# rapidshark-motor-connector-mk-1_1.net
KiCad netlist of a schematic drawn in EAGLE
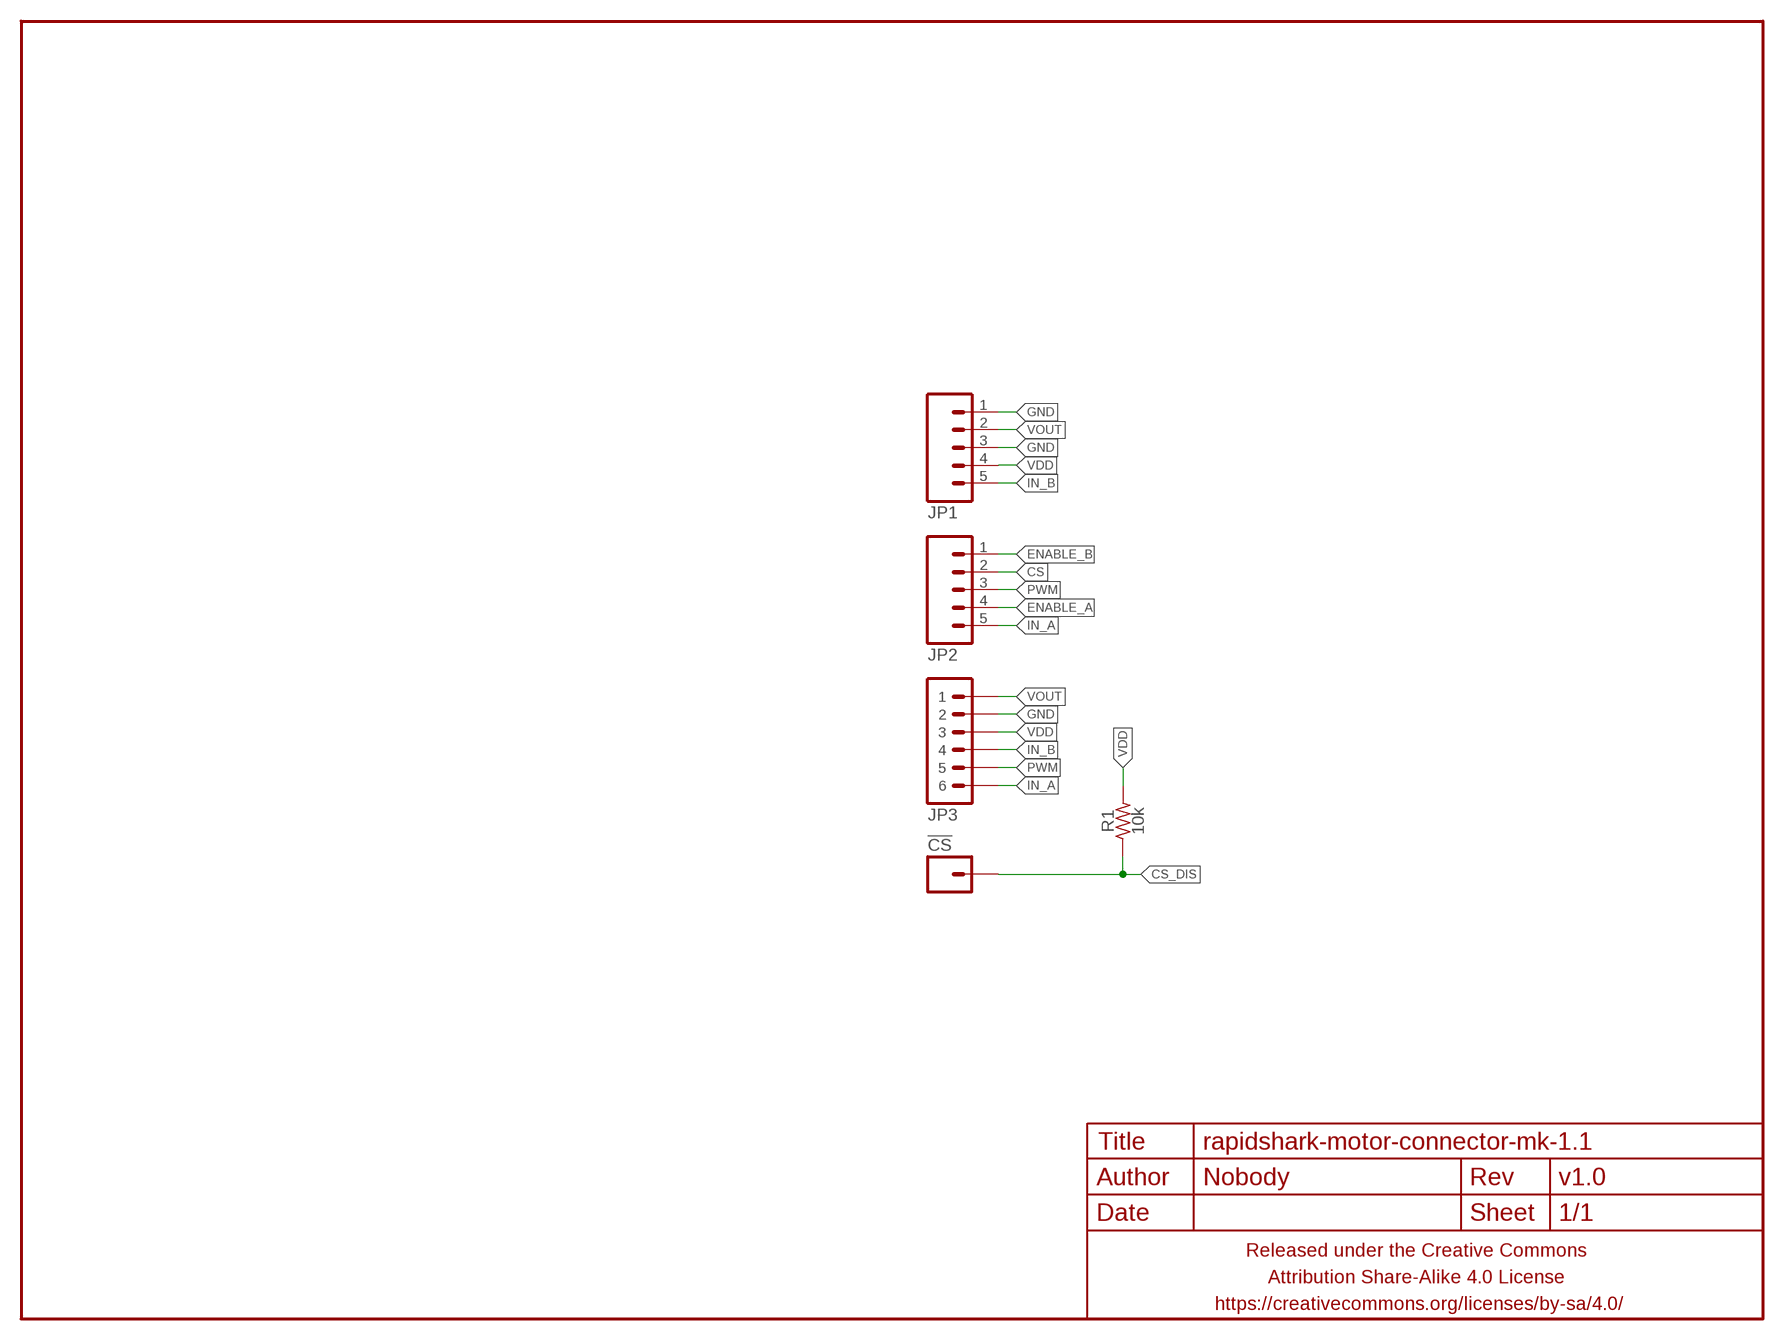
[diagram p0: schematic, sheet 1]

(export (version "E")
  (design (tool "Eeschema 10.0.6"))
  (components
    (comp (ref "!CS")
      (value "M01PTH")
      (footprint "eagle-import:1X01")
      (libsource (lib "eagle-import") (part "M01PTH"))
    )
    (comp (ref "FRAME1")
      (value "FRAME-LETTERNO_PACKAGE")
      (footprint "eagle-import:DUMMY")
      (fields (field (name "VERSION") "v1.0") (field (name "DESIGNER") "Nobody"))
      (libsource (lib "eagle-import") (part "FRAME-LETTERNO_PACKAGE"))
    )
    (comp (ref "JP1")
      (value "M05PTH")
      (footprint "eagle-import:1X05")
      (libsource (lib "eagle-import") (part "M05PTH"))
    )
    (comp (ref "JP2")
      (value "M05PTH")
      (footprint "eagle-import:1X05")
      (libsource (lib "eagle-import") (part "M05PTH"))
    )
    (comp (ref "JP3")
      (value "M06JST-PH-PTH-RA")
      (footprint "eagle-import:JST-6-PH-RA-PTH")
      (libsource (lib "eagle-import") (part "M06JST-PH-PTH-RA"))
    )
    (comp (ref "R1")
      (value "10k")
      (footprint "eagle-import:RESISTOR-AXIAL-PTH-5.08MM")
      (libsource (lib "eagle-import") (part "RESISTORPTH-AXIAL-5.08MM"))
    )
  )
  (nets
    (net (code "1") (name "CS") (class "Default")
      (node (ref "JP2") (pin "2") (pinfunction "2_2") (pintype "passive"))
    )
    (net (code "2") (name "CS_DIS") (class "Default")
      (node (ref "!CS") (pin "1") (pinfunction "1_1") (pintype "passive"))
      (node (ref "R1") (pin "P$1") (pinfunction "1_P$1") (pintype "passive"))
    )
    (net (code "3") (name "ENABLE_A") (class "Default")
      (node (ref "JP2") (pin "4") (pinfunction "4_4") (pintype "passive"))
    )
    (net (code "4") (name "ENABLE_B") (class "Default")
      (node (ref "JP2") (pin "1") (pinfunction "1_1") (pintype "passive"))
    )
    (net (code "5") (name "GND") (class "Default")
      (node (ref "JP1") (pin "1") (pinfunction "1_1") (pintype "passive"))
      (node (ref "JP1") (pin "3") (pinfunction "3_3") (pintype "passive"))
      (node (ref "JP3") (pin "2") (pinfunction "2_2") (pintype "passive"))
    )
    (net (code "6") (name "IN_A") (class "Default")
      (node (ref "JP2") (pin "5") (pinfunction "5_5") (pintype "passive"))
      (node (ref "JP3") (pin "6") (pinfunction "6_6") (pintype "passive"))
    )
    (net (code "7") (name "IN_B") (class "Default")
      (node (ref "JP1") (pin "5") (pinfunction "5_5") (pintype "passive"))
      (node (ref "JP3") (pin "4") (pinfunction "4_4") (pintype "passive"))
    )
    (net (code "8") (name "PWM") (class "Default")
      (node (ref "JP2") (pin "3") (pinfunction "3_3") (pintype "passive"))
      (node (ref "JP3") (pin "5") (pinfunction "5_5") (pintype "passive"))
    )
    (net (code "9") (name "VDD") (class "Default")
      (node (ref "JP1") (pin "4") (pinfunction "4_4") (pintype "passive"))
      (node (ref "JP3") (pin "3") (pinfunction "3_3") (pintype "passive"))
      (node (ref "R1") (pin "P$2") (pinfunction "2_P$2") (pintype "passive"))
    )
    (net (code "10") (name "VOUT") (class "Default")
      (node (ref "JP1") (pin "2") (pinfunction "2_2") (pintype "passive"))
      (node (ref "JP3") (pin "1") (pinfunction "1_1") (pintype "passive"))
    )
  )
)
